# Sheet2.net
KiCad netlist of a schematic drawn in Altium Designer
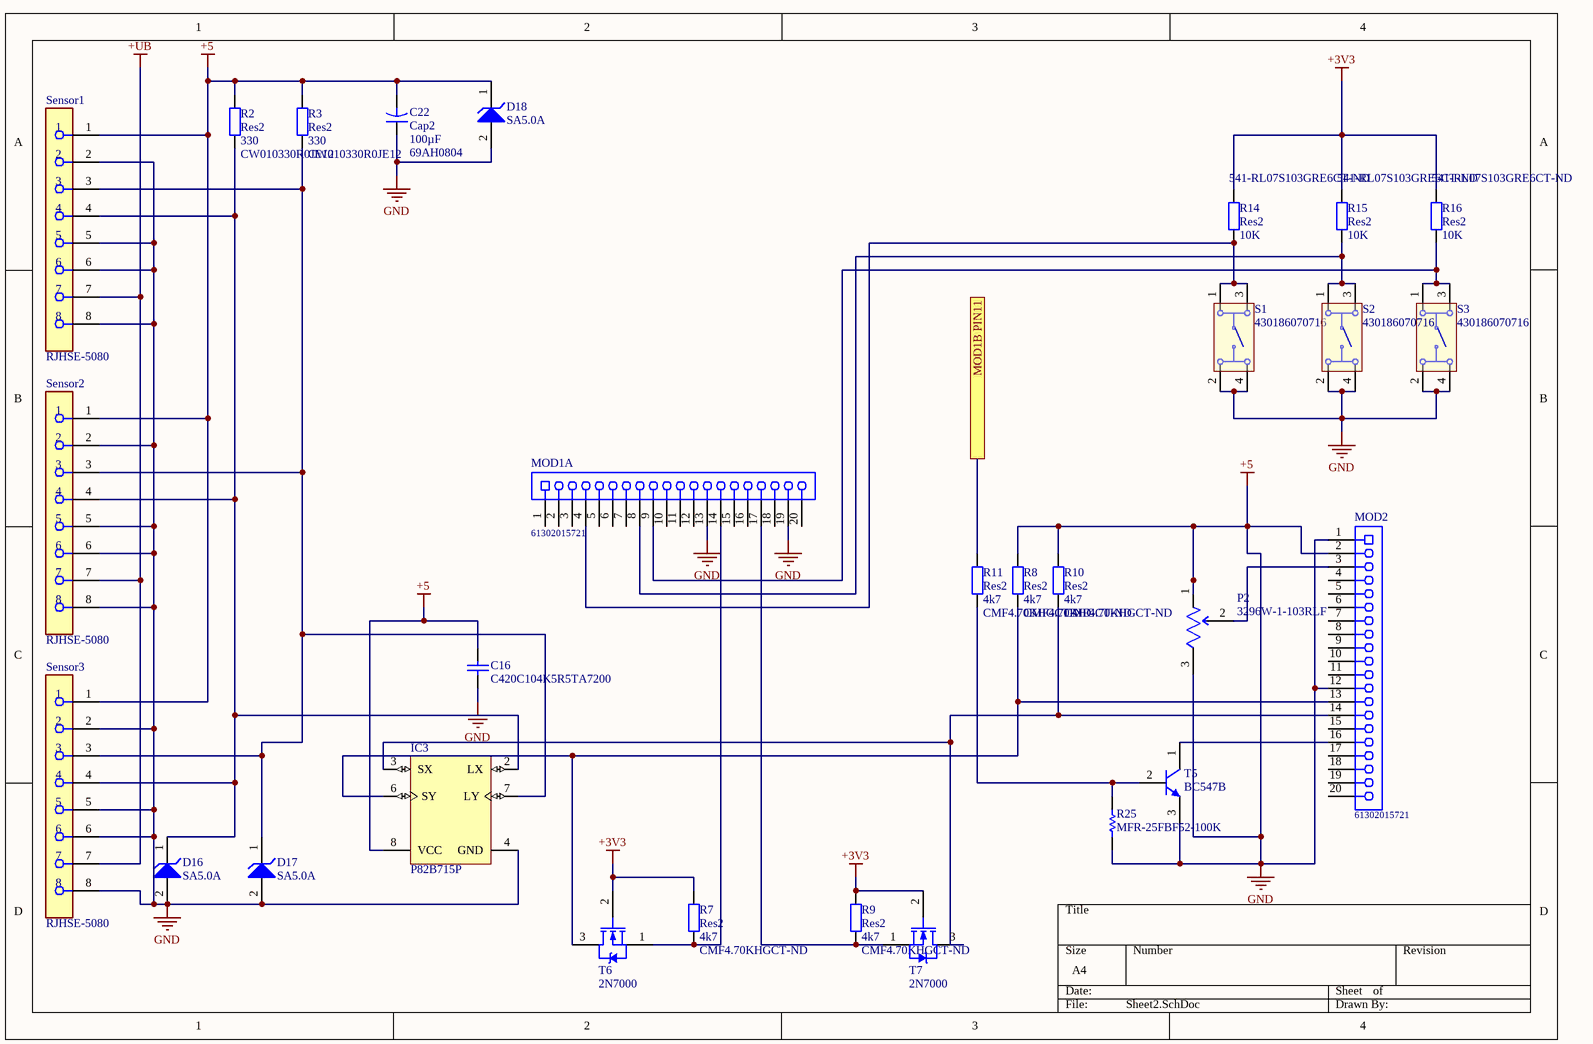
[diagram p0: Sheet2.SchDoc]

(export (version "E")
  (design (tool "Eeschema 10.0.6"))
  (components
    (comp (ref "C16")
      (value "C420C104K5R5TA7200")
      (footprint "KEMT-C420C104K5R5TA7200-2")
      (description "CAP, Ceramic, 0.1 uF, +/- 10%, 50 V, -55 to 125 degC, 2-Pin THD, RoHS, Tape and Reel")
      (fields (field (name "TOLERANCE") "10%") (field (name "MANUFACTURER") "KEMET"))
      (libsource (lib "Altium Content Vault") (part "CAP-NP-2"))
    )
    (comp (ref "C22")
      (value "Cap2")
      (footprint "CAPR5-4X5")
      (description "Cap Aluminum 100uF 25V 20% (6.3 X 11mm) Radial 5mm 190mA 2500 hr 85C Ammo Pack")
      (fields
        (field (name "ALTIUM_VALUE") "100µF")
        (field (name "SUPPLIER PART NUMBER 1") "69AH0804")
        (field (name "MANUFACTURER") "Vishay BCcomponents")
        (field (name "MANUFACTURER PART NUMBER") "MAL203836101E3")
        (field (name "PUBLISHER") "Altium Limited")
      )
      (libsource (lib "Miscellaneous Devices") (part "Cap2"))
    )
    (comp (ref "D16")
      (value "SA5.0A")
      (footprint "ONSC-AXIAL_LEAD-2-59AA-01_P")
      (fields (field (name "MANUFACTURER") "On Semiconductor"))
      (libsource (lib "Altium Content Vault") (part "ONSC-K1A2-2"))
    )
    (comp (ref "D17")
      (value "SA5.0A")
      (footprint "ONSC-AXIAL_LEAD-2-59AA-01_P")
      (fields (field (name "MANUFACTURER") "On Semiconductor"))
      (libsource (lib "Altium Content Vault") (part "ONSC-K1A2-2"))
    )
    (comp (ref "D18")
      (value "SA5.0A")
      (footprint "ONSC-AXIAL_LEAD-2-59AA-01_P")
      (fields (field (name "MANUFACTURER") "On Semiconductor"))
      (libsource (lib "Altium Content Vault") (part "ONSC-K1A2-2"))
    )
    (comp (ref "IC3")
      (value "P82B715P")
      (footprint "P0008A")
      (description "I2C Bus Extender, 2 Channel Width, 3.0 to 12.0 V, -40 to 85 degC, 8-pin PDIP (P), Pb-Free (RoHS)")
      (fields (field (name "MANUFACTURER") "Texas Instruments"))
      (libsource (lib "Altium Content Vault") (part "TI-P82B715-PDIP_P-8"))
    )
    (comp (ref "MOD1A")
      (value "61302015721")
      (footprint "61302015721")
      (description "THT Vertical Socket Header WR-PHD, Pitch 2.54 mm, Single Row, 20 pins")
      (fields (field (name "MANUFACTURER") "Wurth Elektronik") (field (name "PUBLISHER") "WurthElektronik"))
      (libsource (lib "Altium Content Vault") (part "WE-CN-1P-F-R20"))
    )
    (comp (ref "MOD2")
      (value "61302015721")
      (footprint "61302015721")
      (description "THT Vertical Socket Header WR-PHD, Pitch 2.54 mm, Single Row, 20 pins")
      (fields (field (name "MANUFACTURER") "Wurth Elektronik") (field (name "PUBLISHER") "WurthElektronik"))
      (libsource (lib "Altium Content Vault") (part "WE-CN-1P-F-R20"))
    )
    (comp (ref "P2")
      (value "3296W-1-103RLF")
      (footprint "FP-3296W-MFG")
      (description "TRIMMER 10K OHM 0.5W PC PIN TOP")
      (fields (field (name "TOLERANCE") "10%"))
      (libsource (lib "Altium Content Vault") (part "194907ebf2981c0cdd5d9631a0af656"))
    )
    (comp (ref "R2")
      (value "Res2")
      (footprint "AXIAL-0.4")
      (description "Wirewound Resistors 10watts 330ohms 5%")
      (fields
        (field (name "ALTIUM_VALUE") "330")
        (field (name "SUPPLIER PART NUMBER 1") "CW010330R0JE12")
        (field (name "MANUFACTURER") "Vishay Dale")
        (field (name "MANUFACTURER PART NUMBER") "CW010330R0JE12")
        (field (name "PUBLISHER") "Altium Limited")
      )
      (libsource (lib "") (part "Res2_1"))
    )
    (comp (ref "R3")
      (value "Res2")
      (footprint "AXIAL-0.4")
      (description "Wirewound Resistors 10watts 330ohms 5%")
      (fields
        (field (name "ALTIUM_VALUE") "330")
        (field (name "SUPPLIER PART NUMBER 1") "CW010330R0JE12")
        (field (name "MANUFACTURER") "Vishay Dale")
        (field (name "MANUFACTURER PART NUMBER") "CW010330R0JE12")
        (field (name "PUBLISHER") "Altium Limited")
      )
      (libsource (lib "") (part "Res2_1"))
    )
    (comp (ref "R7")
      (value "Res2")
      (footprint "AXIAL-0.4")
      (fields
        (field (name "ALTIUM_VALUE") "4k7")
        (field (name "SUPPLIER PART NUMBER 1") "CMF4.70KHGCT-ND")
        (field (name "MANUFACTURER") "Vishay Dale")
        (field (name "MANUFACTURER PART NUMBER") "CMF554K7000FKEB")
        (field (name "TOLERANCE") "1%")
        (field (name "PUBLISHER") "Altium Limited")
      )
      (libsource (lib "") (part "Res2_1"))
    )
    (comp (ref "R8")
      (value "Res2")
      (footprint "AXIAL-0.4")
      (fields
        (field (name "ALTIUM_VALUE") "4k7")
        (field (name "SUPPLIER PART NUMBER 1") "CMF4.70KHGCT-ND")
        (field (name "MANUFACTURER") "Vishay Dale")
        (field (name "MANUFACTURER PART NUMBER") "CMF554K7000FKEB")
        (field (name "TOLERANCE") "1%")
        (field (name "PUBLISHER") "Altium Limited")
      )
      (libsource (lib "Miscellaneous Devices") (part "Res2"))
    )
    (comp (ref "R9")
      (value "Res2")
      (footprint "AXIAL-0.4")
      (fields
        (field (name "ALTIUM_VALUE") "4k7")
        (field (name "SUPPLIER PART NUMBER 1") "CMF4.70KHGCT-ND")
        (field (name "MANUFACTURER") "Vishay Dale")
        (field (name "MANUFACTURER PART NUMBER") "CMF554K7000FKEB")
        (field (name "TOLERANCE") "1%")
        (field (name "PUBLISHER") "Altium Limited")
      )
      (libsource (lib "Miscellaneous Devices") (part "Res2"))
    )
    (comp (ref "R10")
      (value "Res2")
      (footprint "AXIAL-0.4")
      (fields
        (field (name "ALTIUM_VALUE") "4k7")
        (field (name "SUPPLIER PART NUMBER 1") "CMF4.70KHGCT-ND")
        (field (name "MANUFACTURER") "Vishay Dale")
        (field (name "MANUFACTURER PART NUMBER") "CMF554K7000FKEB")
        (field (name "TOLERANCE") "1%")
        (field (name "PUBLISHER") "Altium Limited")
      )
      (libsource (lib "Miscellaneous Devices") (part "Res2"))
    )
    (comp (ref "R11")
      (value "Res2")
      (footprint "AXIAL-0.4")
      (fields
        (field (name "ALTIUM_VALUE") "4k7")
        (field (name "SUPPLIER PART NUMBER 1") "CMF4.70KHGCT-ND")
        (field (name "MANUFACTURER") "Vishay Dale")
        (field (name "MANUFACTURER PART NUMBER") "CMF554K7000FKEB")
        (field (name "TOLERANCE") "1%")
        (field (name "PUBLISHER") "Altium Limited")
      )
      (libsource (lib "Miscellaneous Devices") (part "Res2"))
    )
    (comp (ref "R14")
      (value "Res2")
      (footprint "AXIAL-0.4")
      (description "Metal Film Resistors 1/4watt 10Kohms 2%")
      (fields
        (field (name "ALTIUM_VALUE") "10K")
        (field (name "SUPPLIER PART NUMBER 1") "541-RL07S103GRE6CT-ND")
        (field (name "MANUFACTURER") "Vishay Dale")
        (field (name "MANUFACTURER PART NUMBER") "RL07S103GRE6")
        (field (name "PUBLISHER") "Altium Limited")
      )
      (libsource (lib "") (part "Res2_1"))
    )
    (comp (ref "R15")
      (value "Res2")
      (footprint "AXIAL-0.4")
      (description "Metal Film Resistors 1/4watt 10Kohms 2%")
      (fields
        (field (name "ALTIUM_VALUE") "10K")
        (field (name "SUPPLIER PART NUMBER 1") "541-RL07S103GRE6CT-ND")
        (field (name "MANUFACTURER") "Vishay Dale")
        (field (name "MANUFACTURER PART NUMBER") "RL07S103GRE6")
        (field (name "PUBLISHER") "Altium Limited")
      )
      (libsource (lib "") (part "Res2_1"))
    )
    (comp (ref "R16")
      (value "Res2")
      (footprint "AXIAL-0.4")
      (description "Metal Film Resistors 1/4watt 10Kohms 2%")
      (fields
        (field (name "ALTIUM_VALUE") "10K")
        (field (name "SUPPLIER PART NUMBER 1") "541-RL07S103GRE6CT-ND")
        (field (name "MANUFACTURER") "Vishay Dale")
        (field (name "MANUFACTURER PART NUMBER") "RL07S103GRE6")
        (field (name "PUBLISHER") "Altium Limited")
      )
      (libsource (lib "") (part "Res2_1"))
    )
    (comp (ref "R25")
      (value "MFR-25FBF52-100K")
      (footprint "RESA60-630X240")
      (description "Axial Resistor, 100 KOhm, +/- 1%, 0.25 W, -55 to 155 degC, 2-Pin THD, RoHS, Bulk")
      (fields (field (name "TOLERANCE") "1%"))
      (libsource (lib "Altium Content Vault") (part "RES-2"))
    )
    (comp (ref "S1")
      (value "430186070716")
      (footprint "430186070716")
      (description "WS-TATV THT Tact Switch 6X6 mm")
      (fields (field (name "MANUFACTURER") "Wuerth Elektronik"))
      (libsource (lib "Altium Content Vault") (part "WE-TACT-SW-4"))
    )
    (comp (ref "S2")
      (value "430186070716")
      (footprint "430186070716")
      (description "WS-TATV THT Tact Switch 6X6 mm")
      (fields (field (name "MANUFACTURER") "Wuerth Elektronik"))
      (libsource (lib "Altium Content Vault") (part "WE-TACT-SW-4"))
    )
    (comp (ref "S3")
      (value "430186070716")
      (footprint "430186070716")
      (description "WS-TATV THT Tact Switch 6X6 mm")
      (fields (field (name "MANUFACTURER") "Wuerth Elektronik"))
      (libsource (lib "Altium Content Vault") (part "WE-TACT-SW-4"))
    )
    (comp (ref "Sensor1")
      (value "RJHSE-5080")
      (footprint "FP-RJHSE-5080-MFG")
      (description "CONN MOD JACK 8P8C R/A UNSHLD")
      (fields
        (field (name "OCTOPART") "https://octopart.com/rjhse-5080-amphenol-45060")
        (field (name "MANUFACTURER") "Amphenol")
      )
      (libsource (lib "Altium Content Vault") (part "b0a0b555dd3abf3683e7c330df25cc4"))
    )
    (comp (ref "Sensor2")
      (value "RJHSE-5080")
      (footprint "FP-RJHSE-5080-MFG")
      (description "CONN MOD JACK 8P8C R/A UNSHLD")
      (fields
        (field (name "OCTOPART") "https://octopart.com/rjhse-5080-amphenol-45060")
        (field (name "MANUFACTURER") "Amphenol")
      )
      (libsource (lib "Altium Content Vault") (part "b0a0b555dd3abf3683e7c330df25cc4"))
    )
    (comp (ref "Sensor3")
      (value "RJHSE-5080")
      (footprint "FP-RJHSE-5080-MFG")
      (description "CONN MOD JACK 8P8C R/A UNSHLD")
      (fields
        (field (name "OCTOPART") "https://octopart.com/rjhse-5080-amphenol-45060")
        (field (name "MANUFACTURER") "Amphenol")
      )
      (libsource (lib "Altium Content Vault") (part "b0a0b555dd3abf3683e7c330df25cc4"))
    )
    (comp (ref "T5")
      (value "BC547B")
      (footprint "ONSC-TO-92-3-29-11")
      (description "Amplifier Transistor, NPN Silicon, 3-Pin TO-92, Bulk Box")
      (fields (field (name "MANUFACTURER") "On Semiconductor"))
      (libsource (lib "Altium Content Vault") (part "ONSC-NPN-C1B2E3-3"))
    )
    (comp (ref "T6")
      (value "2N7000")
      (footprint "ONSC-TO-92-3-29-11")
      (description "Small Signal MOSFET, 200 mA, 60 V, N-Channel, 3-Pin TO-92, Bulk Box")
      (fields (field (name "MANUFACTURER") "On Semiconductor"))
      (libsource (lib "Altium Content Vault") (part "ONSC-NMOS-S1G2D3-3"))
    )
    (comp (ref "T7")
      (value "2N7000")
      (footprint "ONSC-TO-92-3-29-11")
      (description "Small Signal MOSFET, 200 mA, 60 V, N-Channel, 3-Pin TO-92, Bulk Box")
      (fields (field (name "MANUFACTURER") "On Semiconductor"))
      (libsource (lib "Altium Content Vault") (part "ONSC-NMOS-S1G2D3-3"))
    )
  )
  (nets
    (net (code "1") (name "+3V3") (class "Default")
      (node (ref "R14") (pin "2") (pinfunction "2_2") (pintype "passive"))
      (node (ref "R15") (pin "2") (pinfunction "2_2") (pintype "passive"))
      (node (ref "R16") (pin "2") (pinfunction "2_2") (pintype "passive"))
      (node (ref "R7") (pin "2") (pinfunction "2_2") (pintype "passive"))
      (node (ref "R9") (pin "1") (pinfunction "1_1") (pintype "passive"))
      (node (ref "T6") (pin "2") (pinfunction "G_2") (pintype "passive"))
      (node (ref "T7") (pin "2") (pinfunction "G_2") (pintype "passive"))
    )
    (net (code "2") (name "+5") (class "Default")
      (node (ref "C16") (pin "1") (pinfunction "1_1") (pintype "passive"))
      (node (ref "C16") (pin "2") (pinfunction "2_2") (pintype "passive"))
      (node (ref "C22") (pin "1") (pinfunction "1_1") (pintype "passive"))
      (node (ref "C22") (pin "2") (pinfunction "2_2") (pintype "passive"))
      (node (ref "D16") (pin "2") (pinfunction "A_2") (pintype "passive"))
      (node (ref "D17") (pin "2") (pinfunction "A_2") (pintype "passive"))
      (node (ref "D18") (pin "1") (pinfunction "K_1") (pintype "passive"))
      (node (ref "D18") (pin "2") (pinfunction "A_2") (pintype "passive"))
      (node (ref "IC3") (pin "4") (pinfunction "GND_4") (pintype "power_in"))
      (node (ref "IC3") (pin "8") (pinfunction "VCC_8") (pintype "power_in"))
      (node (ref "MOD1A") (pin "13") (pinfunction "13_13") (pintype "passive"))
      (node (ref "MOD1A") (pin "19") (pinfunction "19_19") (pintype "passive"))
      (node (ref "MOD2") (pin "1") (pinfunction "1_1") (pintype "passive"))
      (node (ref "MOD2") (pin "12") (pinfunction "12_12") (pintype "passive"))
      (node (ref "MOD2") (pin "2") (pinfunction "2_2") (pintype "passive"))
      (node (ref "P2") (pin "1") (pinfunction "CCW_1") (pintype "passive"))
      (node (ref "P2") (pin "3") (pinfunction "CW_3") (pintype "passive"))
      (node (ref "R10") (pin "1") (pinfunction "1_1") (pintype "passive"))
      (node (ref "R2") (pin "2") (pinfunction "2_2") (pintype "passive"))
      (node (ref "R25") (pin "1") (pinfunction "1_1") (pintype "passive"))
      (node (ref "R3") (pin "2") (pinfunction "2_2") (pintype "passive"))
      (node (ref "R8") (pin "1") (pinfunction "1_1") (pintype "passive"))
      (node (ref "S1") (pin "2") (pinfunction "2_2") (pintype "passive"))
      (node (ref "S1") (pin "4") (pinfunction "4_4") (pintype "passive"))
      (node (ref "S2") (pin "2") (pinfunction "2_2") (pintype "passive"))
      (node (ref "S2") (pin "4") (pinfunction "4_4") (pintype "passive"))
      (node (ref "S3") (pin "2") (pinfunction "2_2") (pintype "passive"))
      (node (ref "S3") (pin "4") (pinfunction "4_4") (pintype "passive"))
      (node (ref "Sensor1") (pin "1") (pinfunction "1_1") (pintype "passive"))
      (node (ref "Sensor1") (pin "2") (pinfunction "2_2") (pintype "passive"))
      (node (ref "Sensor1") (pin "5") (pinfunction "5_5") (pintype "passive"))
      (node (ref "Sensor1") (pin "6") (pinfunction "6_6") (pintype "passive"))
      (node (ref "Sensor1") (pin "8") (pinfunction "8_8") (pintype "passive"))
      (node (ref "Sensor2") (pin "1") (pinfunction "1_1") (pintype "passive"))
      (node (ref "Sensor2") (pin "2") (pinfunction "2_2") (pintype "passive"))
      (node (ref "Sensor2") (pin "5") (pinfunction "5_5") (pintype "passive"))
      (node (ref "Sensor2") (pin "6") (pinfunction "6_6") (pintype "passive"))
      (node (ref "Sensor2") (pin "8") (pinfunction "8_8") (pintype "passive"))
      (node (ref "Sensor3") (pin "1") (pinfunction "1_1") (pintype "passive"))
      (node (ref "Sensor3") (pin "2") (pinfunction "2_2") (pintype "passive"))
      (node (ref "Sensor3") (pin "5") (pinfunction "5_5") (pintype "passive"))
      (node (ref "Sensor3") (pin "6") (pinfunction "6_6") (pintype "passive"))
      (node (ref "Sensor3") (pin "8") (pinfunction "8_8") (pintype "passive"))
      (node (ref "T5") (pin "3") (pinfunction "E_3") (pintype "passive"))
    )
    (net (code "3") (name "+UB") (class "Default")
      (node (ref "Sensor1") (pin "7") (pinfunction "7_7") (pintype "passive"))
      (node (ref "Sensor2") (pin "7") (pinfunction "7_7") (pintype "passive"))
      (node (ref "Sensor3") (pin "7") (pinfunction "7_7") (pintype "passive"))
    )
    (net (code "4") (name "/MOD1B PIN11") (class "Default")
      (node (ref "R11") (pin "1") (pinfunction "1_1") (pintype "passive"))
    )
    (net (code "5") (name "Net-(D16-K)") (class "Default")
      (node (ref "D16") (pin "1") (pinfunction "K_1") (pintype "passive"))
      (node (ref "IC3") (pin "2") (pinfunction "LX_2") (pintype "bidirectional"))
      (node (ref "R2") (pin "1") (pinfunction "1_1") (pintype "passive"))
      (node (ref "Sensor1") (pin "4") (pinfunction "4_4") (pintype "passive"))
      (node (ref "Sensor2") (pin "4") (pinfunction "4_4") (pintype "passive"))
      (node (ref "Sensor3") (pin "4") (pinfunction "4_4") (pintype "passive"))
    )
    (net (code "6") (name "Net-(D17-K)") (class "Default")
      (node (ref "D17") (pin "1") (pinfunction "K_1") (pintype "passive"))
      (node (ref "IC3") (pin "7") (pinfunction "LY_7") (pintype "bidirectional"))
      (node (ref "R3") (pin "1") (pinfunction "1_1") (pintype "passive"))
      (node (ref "Sensor1") (pin "3") (pinfunction "3_3") (pintype "passive"))
      (node (ref "Sensor2") (pin "3") (pinfunction "3_3") (pintype "passive"))
      (node (ref "Sensor3") (pin "3") (pinfunction "3_3") (pintype "passive"))
    )
    (net (code "7") (name "Net-(IC3-SX)") (class "Default")
      (node (ref "IC3") (pin "3") (pinfunction "SX_3") (pintype "bidirectional"))
      (node (ref "MOD2") (pin "14") (pinfunction "14_14") (pintype "passive"))
      (node (ref "R10") (pin "2") (pinfunction "2_2") (pintype "passive"))
      (node (ref "T7") (pin "3") (pinfunction "D_3") (pintype "passive"))
    )
    (net (code "8") (name "Net-(IC3-SY)") (class "Default")
      (node (ref "IC3") (pin "6") (pinfunction "SY_6") (pintype "bidirectional"))
      (node (ref "MOD2") (pin "13") (pinfunction "13_13") (pintype "passive"))
      (node (ref "R8") (pin "2") (pinfunction "2_2") (pintype "passive"))
      (node (ref "T6") (pin "3") (pinfunction "D_3") (pintype "passive"))
    )
    (net (code "9") (name "Net-(MOD1A-Pad4)") (class "Default")
      (node (ref "MOD1A") (pin "4") (pinfunction "4_4") (pintype "passive"))
      (node (ref "R14") (pin "1") (pinfunction "1_1") (pintype "passive"))
      (node (ref "S1") (pin "1") (pinfunction "1_1") (pintype "passive"))
      (node (ref "S1") (pin "3") (pinfunction "3_3") (pintype "passive"))
    )
    (net (code "10") (name "Net-(MOD1A-Pad8)") (class "Default")
      (node (ref "MOD1A") (pin "8") (pinfunction "8_8") (pintype "passive"))
      (node (ref "R15") (pin "1") (pinfunction "1_1") (pintype "passive"))
      (node (ref "S2") (pin "1") (pinfunction "1_1") (pintype "passive"))
      (node (ref "S2") (pin "3") (pinfunction "3_3") (pintype "passive"))
    )
    (net (code "11") (name "Net-(MOD1A-Pad9)") (class "Default")
      (node (ref "MOD1A") (pin "9") (pinfunction "9_9") (pintype "passive"))
      (node (ref "R16") (pin "1") (pinfunction "1_1") (pintype "passive"))
      (node (ref "S3") (pin "1") (pinfunction "1_1") (pintype "passive"))
      (node (ref "S3") (pin "3") (pinfunction "3_3") (pintype "passive"))
    )
    (net (code "12") (name "Net-(P2-WIPER)") (class "Default")
      (node (ref "MOD2") (pin "3") (pinfunction "3_3") (pintype "passive"))
      (node (ref "P2") (pin "2") (pinfunction "WIPER_2") (pintype "passive"))
    )
    (net (code "13") (name "Net-(T5-B)") (class "Default")
      (node (ref "R11") (pin "2") (pinfunction "2_2") (pintype "passive"))
      (node (ref "R25") (pin "2") (pinfunction "2_2") (pintype "passive"))
      (node (ref "T5") (pin "2") (pinfunction "B_2") (pintype "passive"))
    )
    (net (code "14") (name "Net-(T5-C)") (class "Default")
      (node (ref "MOD2") (pin "16") (pinfunction "16_16") (pintype "passive"))
      (node (ref "T5") (pin "1") (pinfunction "C_1") (pintype "passive"))
    )
    (net (code "15") (name "Net-(T6-S)") (class "Default")
      (node (ref "MOD1A") (pin "14") (pinfunction "14_14") (pintype "passive"))
      (node (ref "R7") (pin "1") (pinfunction "1_1") (pintype "passive"))
      (node (ref "T6") (pin "1") (pinfunction "S_1") (pintype "passive"))
    )
    (net (code "16") (name "Net-(T7-S)") (class "Default")
      (node (ref "MOD1A") (pin "17") (pinfunction "17_17") (pintype "passive"))
      (node (ref "R9") (pin "2") (pinfunction "2_2") (pintype "passive"))
      (node (ref "T7") (pin "1") (pinfunction "S_1") (pintype "passive"))
    )
    (net (code "17") (name "unconnected-(MOD1A-Pad1)") (class "Default")
      (node (ref "MOD1A") (pin "1") (pinfunction "1_1") (pintype "passive"))
    )
    (net (code "18") (name "unconnected-(MOD1A-Pad2)") (class "Default")
      (node (ref "MOD1A") (pin "2") (pinfunction "2_2") (pintype "passive"))
    )
    (net (code "19") (name "unconnected-(MOD1A-Pad3)") (class "Default")
      (node (ref "MOD1A") (pin "3") (pinfunction "3_3") (pintype "passive"))
    )
    (net (code "20") (name "unconnected-(MOD1A-Pad5)") (class "Default")
      (node (ref "MOD1A") (pin "5") (pinfunction "5_5") (pintype "passive"))
    )
    (net (code "21") (name "unconnected-(MOD1A-Pad6)") (class "Default")
      (node (ref "MOD1A") (pin "6") (pinfunction "6_6") (pintype "passive"))
    )
    (net (code "22") (name "unconnected-(MOD1A-Pad7)") (class "Default")
      (node (ref "MOD1A") (pin "7") (pinfunction "7_7") (pintype "passive"))
    )
    (net (code "23") (name "unconnected-(MOD1A-Pad10)") (class "Default")
      (node (ref "MOD1A") (pin "10") (pinfunction "10_10") (pintype "passive"))
    )
    (net (code "24") (name "unconnected-(MOD1A-Pad11)") (class "Default")
      (node (ref "MOD1A") (pin "11") (pinfunction "11_11") (pintype "passive"))
    )
    (net (code "25") (name "unconnected-(MOD1A-Pad12)") (class "Default")
      (node (ref "MOD1A") (pin "12") (pinfunction "12_12") (pintype "passive"))
    )
    (net (code "26") (name "unconnected-(MOD1A-Pad15)") (class "Default")
      (node (ref "MOD1A") (pin "15") (pinfunction "15_15") (pintype "passive"))
    )
    (net (code "27") (name "unconnected-(MOD1A-Pad16)") (class "Default")
      (node (ref "MOD1A") (pin "16") (pinfunction "16_16") (pintype "passive"))
    )
    (net (code "28") (name "unconnected-(MOD1A-Pad18)") (class "Default")
      (node (ref "MOD1A") (pin "18") (pinfunction "18_18") (pintype "passive"))
    )
    (net (code "29") (name "unconnected-(MOD1A-Pad20)") (class "Default")
      (node (ref "MOD1A") (pin "20") (pinfunction "20_20") (pintype "passive"))
    )
    (net (code "30") (name "unconnected-(MOD2-Pad4)") (class "Default")
      (node (ref "MOD2") (pin "4") (pinfunction "4_4") (pintype "passive"))
    )
    (net (code "31") (name "unconnected-(MOD2-Pad5)") (class "Default")
      (node (ref "MOD2") (pin "5") (pinfunction "5_5") (pintype "passive"))
    )
    (net (code "32") (name "unconnected-(MOD2-Pad6)") (class "Default")
      (node (ref "MOD2") (pin "6") (pinfunction "6_6") (pintype "passive"))
    )
    (net (code "33") (name "unconnected-(MOD2-Pad7)") (class "Default")
      (node (ref "MOD2") (pin "7") (pinfunction "7_7") (pintype "passive"))
    )
    (net (code "34") (name "unconnected-(MOD2-Pad8)") (class "Default")
      (node (ref "MOD2") (pin "8") (pinfunction "8_8") (pintype "passive"))
    )
    (net (code "35") (name "unconnected-(MOD2-Pad9)") (class "Default")
      (node (ref "MOD2") (pin "9") (pinfunction "9_9") (pintype "passive"))
    )
    (net (code "36") (name "unconnected-(MOD2-Pad10)") (class "Default")
      (node (ref "MOD2") (pin "10") (pinfunction "10_10") (pintype "passive"))
    )
    (net (code "37") (name "unconnected-(MOD2-Pad11)") (class "Default")
      (node (ref "MOD2") (pin "11") (pinfunction "11_11") (pintype "passive"))
    )
    (net (code "38") (name "unconnected-(MOD2-Pad15)") (class "Default")
      (node (ref "MOD2") (pin "15") (pinfunction "15_15") (pintype "passive"))
    )
    (net (code "39") (name "unconnected-(MOD2-Pad17)") (class "Default")
      (node (ref "MOD2") (pin "17") (pinfunction "17_17") (pintype "passive"))
    )
    (net (code "40") (name "unconnected-(MOD2-Pad18)") (class "Default")
      (node (ref "MOD2") (pin "18") (pinfunction "18_18") (pintype "passive"))
    )
    (net (code "41") (name "unconnected-(MOD2-Pad19)") (class "Default")
      (node (ref "MOD2") (pin "19") (pinfunction "19_19") (pintype "passive"))
    )
    (net (code "42") (name "unconnected-(MOD2-Pad20)") (class "Default")
      (node (ref "MOD2") (pin "20") (pinfunction "20_20") (pintype "passive"))
    )
  )
)
